# DAT_Replacement.net
KiCad netlist of a schematic drawn in EAGLE
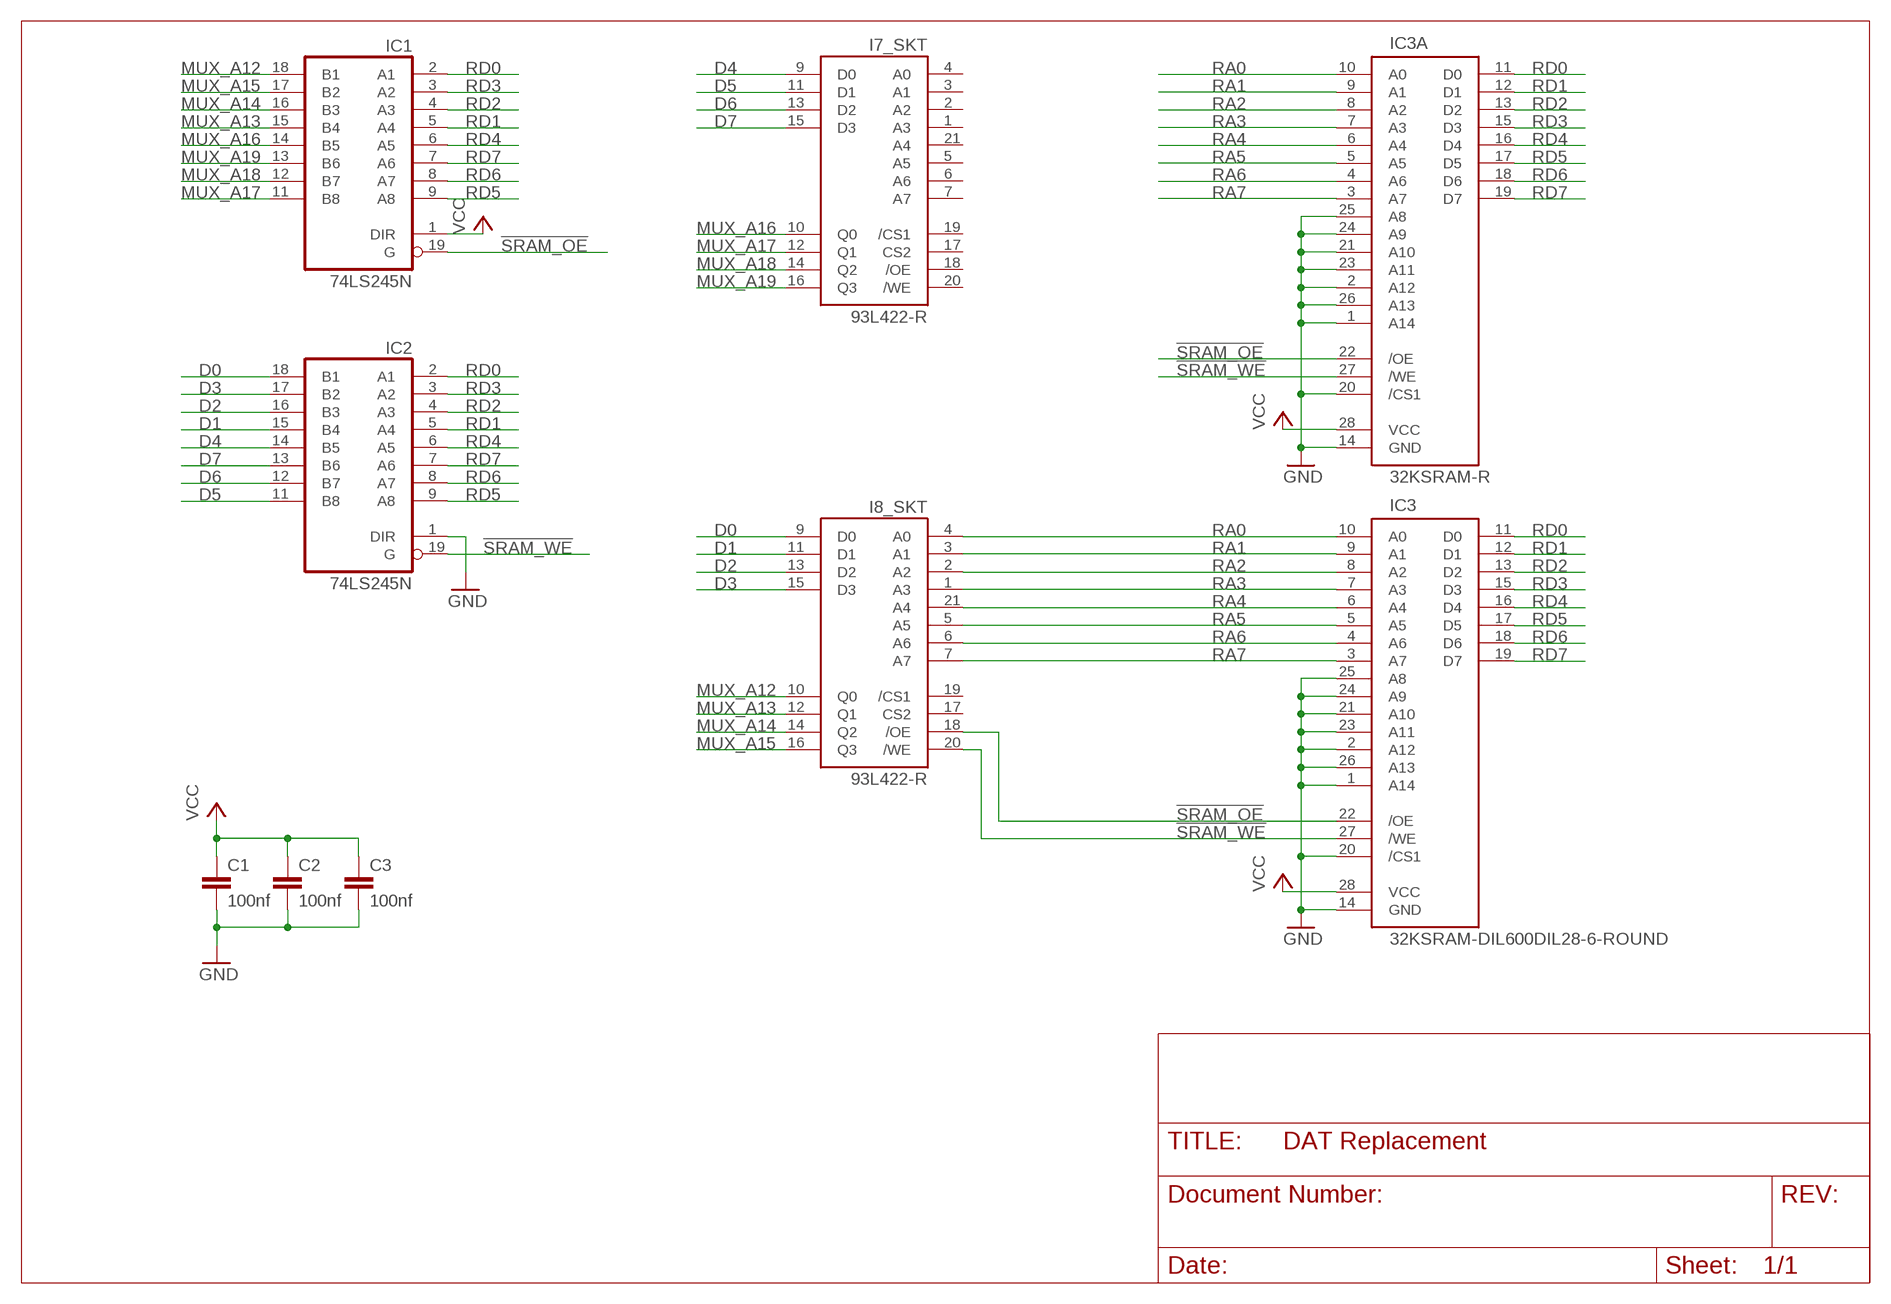
[diagram p0: schematic, sheet 1]

(export (version "E")
  (design (tool "Eeschema 10.0.6"))
  (components
    (comp (ref "C1")
      (value "100nf")
      (footprint "eagle-import:C025-025X050")
      (libsource (lib "eagle-import") (part "C-EU025-025X050"))
    )
    (comp (ref "C2")
      (value "100nf")
      (footprint "eagle-import:C025-025X050")
      (libsource (lib "eagle-import") (part "C-EU025-025X050"))
    )
    (comp (ref "C3")
      (value "100nf")
      (footprint "eagle-import:C025-025X050")
      (libsource (lib "eagle-import") (part "C-EU025-025X050"))
    )
    (comp (ref "I7_SKT")
      (value "93L422-R")
      (footprint "eagle-import:DIL-22-4-ROUND")
      (libsource (lib "eagle-import") (part "93L422-R"))
    )
    (comp (ref "I8_SKT")
      (value "93L422-R")
      (footprint "eagle-import:DIL-22-4-ROUND")
      (libsource (lib "eagle-import") (part "93L422-R"))
    )
    (comp (ref "IC1")
      (value "74LS245N")
      (footprint "eagle-import:DIL20")
      (libsource (lib "eagle-import") (part "74245NLS"))
    )
    (comp (ref "IC2")
      (value "74LS245N")
      (footprint "eagle-import:DIL20")
      (libsource (lib "eagle-import") (part "74245NLS"))
    )
    (comp (ref "IC3")
      (value "32KSRAM-DIL600DIL28-6-ROUND")
      (footprint "eagle-import:DIL28-6-ROUND")
      (libsource (lib "eagle-import") (part "32KSRAM-DIL600DIL28-6-ROUND"))
    )
    (comp (ref "IC3A")
      (value "32KSRAM-R")
      (footprint "eagle-import:DIL28-3-ROUND")
      (libsource (lib "eagle-import") (part "32KSRAM-R"))
    )
  )
  (nets
    (net (code "1") (name "/D0") (class "Default")
      (node (ref "I8_SKT") (pin "9") (pinfunction "D0_9") (pintype "input"))
      (node (ref "IC2") (pin "18") (pinfunction "B1_18") (pintype "bidirectional"))
    )
    (net (code "2") (name "/D1") (class "Default")
      (node (ref "I8_SKT") (pin "11") (pinfunction "D1_11") (pintype "input"))
      (node (ref "IC2") (pin "15") (pinfunction "B4_15") (pintype "bidirectional"))
    )
    (net (code "3") (name "/D2") (class "Default")
      (node (ref "I8_SKT") (pin "13") (pinfunction "D2_13") (pintype "input"))
      (node (ref "IC2") (pin "16") (pinfunction "B3_16") (pintype "bidirectional"))
    )
    (net (code "4") (name "/D3") (class "Default")
      (node (ref "I8_SKT") (pin "15") (pinfunction "D3_15") (pintype "input"))
      (node (ref "IC2") (pin "17") (pinfunction "B2_17") (pintype "bidirectional"))
    )
    (net (code "5") (name "/D4") (class "Default")
      (node (ref "I7_SKT") (pin "9") (pinfunction "D0_9") (pintype "input"))
      (node (ref "IC2") (pin "14") (pinfunction "B5_14") (pintype "bidirectional"))
    )
    (net (code "6") (name "/D5") (class "Default")
      (node (ref "I7_SKT") (pin "11") (pinfunction "D1_11") (pintype "input"))
      (node (ref "IC2") (pin "11") (pinfunction "B8_11") (pintype "bidirectional"))
    )
    (net (code "7") (name "/D6") (class "Default")
      (node (ref "I7_SKT") (pin "13") (pinfunction "D2_13") (pintype "input"))
      (node (ref "IC2") (pin "12") (pinfunction "B7_12") (pintype "bidirectional"))
    )
    (net (code "8") (name "/D7") (class "Default")
      (node (ref "I7_SKT") (pin "15") (pinfunction "D3_15") (pintype "input"))
      (node (ref "IC2") (pin "13") (pinfunction "B6_13") (pintype "bidirectional"))
    )
    (net (code "9") (name "/MUX_A12") (class "Default")
      (node (ref "I8_SKT") (pin "10") (pinfunction "Q0_10") (pintype "output"))
      (node (ref "IC1") (pin "18") (pinfunction "B1_18") (pintype "bidirectional"))
    )
    (net (code "10") (name "/MUX_A13") (class "Default")
      (node (ref "I8_SKT") (pin "12") (pinfunction "Q1_12") (pintype "output"))
      (node (ref "IC1") (pin "15") (pinfunction "B4_15") (pintype "bidirectional"))
    )
    (net (code "11") (name "/MUX_A14") (class "Default")
      (node (ref "I8_SKT") (pin "14") (pinfunction "Q2_14") (pintype "output"))
      (node (ref "IC1") (pin "16") (pinfunction "B3_16") (pintype "bidirectional"))
    )
    (net (code "12") (name "/MUX_A15") (class "Default")
      (node (ref "I8_SKT") (pin "16") (pinfunction "Q3_16") (pintype "output"))
      (node (ref "IC1") (pin "17") (pinfunction "B2_17") (pintype "bidirectional"))
    )
    (net (code "13") (name "/MUX_A16") (class "Default")
      (node (ref "I7_SKT") (pin "10") (pinfunction "Q0_10") (pintype "output"))
      (node (ref "IC1") (pin "14") (pinfunction "B5_14") (pintype "bidirectional"))
    )
    (net (code "14") (name "/MUX_A17") (class "Default")
      (node (ref "I7_SKT") (pin "12") (pinfunction "Q1_12") (pintype "output"))
      (node (ref "IC1") (pin "11") (pinfunction "B8_11") (pintype "bidirectional"))
    )
    (net (code "15") (name "/MUX_A18") (class "Default")
      (node (ref "I7_SKT") (pin "14") (pinfunction "Q2_14") (pintype "output"))
      (node (ref "IC1") (pin "12") (pinfunction "B7_12") (pintype "bidirectional"))
    )
    (net (code "16") (name "/MUX_A19") (class "Default")
      (node (ref "I7_SKT") (pin "16") (pinfunction "Q3_16") (pintype "output"))
      (node (ref "IC1") (pin "13") (pinfunction "B6_13") (pintype "bidirectional"))
    )
    (net (code "17") (name "/RA0") (class "Default")
      (node (ref "I8_SKT") (pin "4") (pinfunction "A0_4") (pintype "input"))
      (node (ref "IC3") (pin "10") (pinfunction "A0_10") (pintype "input"))
      (node (ref "IC3A") (pin "10") (pinfunction "A0_10") (pintype "input"))
    )
    (net (code "18") (name "/RA1") (class "Default")
      (node (ref "I8_SKT") (pin "3") (pinfunction "A1_3") (pintype "input"))
      (node (ref "IC3") (pin "9") (pinfunction "A1_9") (pintype "input"))
      (node (ref "IC3A") (pin "9") (pinfunction "A1_9") (pintype "input"))
    )
    (net (code "19") (name "/RA2") (class "Default")
      (node (ref "I8_SKT") (pin "2") (pinfunction "A2_2") (pintype "input"))
      (node (ref "IC3") (pin "8") (pinfunction "A2_8") (pintype "input"))
      (node (ref "IC3A") (pin "8") (pinfunction "A2_8") (pintype "input"))
    )
    (net (code "20") (name "/RA3") (class "Default")
      (node (ref "I8_SKT") (pin "1") (pinfunction "A3_1") (pintype "input"))
      (node (ref "IC3") (pin "7") (pinfunction "A3_7") (pintype "input"))
      (node (ref "IC3A") (pin "7") (pinfunction "A3_7") (pintype "input"))
    )
    (net (code "21") (name "/RA4") (class "Default")
      (node (ref "I8_SKT") (pin "21") (pinfunction "A4_21") (pintype "input"))
      (node (ref "IC3") (pin "6") (pinfunction "A4_6") (pintype "input"))
      (node (ref "IC3A") (pin "6") (pinfunction "A4_6") (pintype "input"))
    )
    (net (code "22") (name "/RA5") (class "Default")
      (node (ref "I8_SKT") (pin "5") (pinfunction "A5_5") (pintype "input"))
      (node (ref "IC3") (pin "5") (pinfunction "A5_5") (pintype "input"))
      (node (ref "IC3A") (pin "5") (pinfunction "A5_5") (pintype "input"))
    )
    (net (code "23") (name "/RA6") (class "Default")
      (node (ref "I8_SKT") (pin "6") (pinfunction "A6_6") (pintype "input"))
      (node (ref "IC3") (pin "4") (pinfunction "A6_4") (pintype "input"))
      (node (ref "IC3A") (pin "4") (pinfunction "A6_4") (pintype "input"))
    )
    (net (code "24") (name "/RA7") (class "Default")
      (node (ref "I8_SKT") (pin "7") (pinfunction "A7_7") (pintype "input"))
      (node (ref "IC3") (pin "3") (pinfunction "A7_3") (pintype "input"))
      (node (ref "IC3A") (pin "3") (pinfunction "A7_3") (pintype "input"))
    )
    (net (code "25") (name "/RD0") (class "Default")
      (node (ref "IC1") (pin "2") (pinfunction "A1_2") (pintype "bidirectional"))
      (node (ref "IC2") (pin "2") (pinfunction "A1_2") (pintype "bidirectional"))
      (node (ref "IC3") (pin "11") (pinfunction "D0_11") (pintype "bidirectional"))
      (node (ref "IC3A") (pin "11") (pinfunction "D0_11") (pintype "bidirectional"))
    )
    (net (code "26") (name "/RD1") (class "Default")
      (node (ref "IC1") (pin "5") (pinfunction "A4_5") (pintype "bidirectional"))
      (node (ref "IC2") (pin "5") (pinfunction "A4_5") (pintype "bidirectional"))
      (node (ref "IC3") (pin "12") (pinfunction "D1_12") (pintype "bidirectional"))
      (node (ref "IC3A") (pin "12") (pinfunction "D1_12") (pintype "bidirectional"))
    )
    (net (code "27") (name "/RD2") (class "Default")
      (node (ref "IC1") (pin "4") (pinfunction "A3_4") (pintype "bidirectional"))
      (node (ref "IC2") (pin "4") (pinfunction "A3_4") (pintype "bidirectional"))
      (node (ref "IC3") (pin "13") (pinfunction "D2_13") (pintype "bidirectional"))
      (node (ref "IC3A") (pin "13") (pinfunction "D2_13") (pintype "bidirectional"))
    )
    (net (code "28") (name "/RD3") (class "Default")
      (node (ref "IC1") (pin "3") (pinfunction "A2_3") (pintype "bidirectional"))
      (node (ref "IC2") (pin "3") (pinfunction "A2_3") (pintype "bidirectional"))
      (node (ref "IC3") (pin "15") (pinfunction "D3_15") (pintype "bidirectional"))
      (node (ref "IC3A") (pin "15") (pinfunction "D3_15") (pintype "bidirectional"))
    )
    (net (code "29") (name "/RD4") (class "Default")
      (node (ref "IC1") (pin "6") (pinfunction "A5_6") (pintype "bidirectional"))
      (node (ref "IC2") (pin "6") (pinfunction "A5_6") (pintype "bidirectional"))
      (node (ref "IC3") (pin "16") (pinfunction "D4_16") (pintype "bidirectional"))
      (node (ref "IC3A") (pin "16") (pinfunction "D4_16") (pintype "bidirectional"))
    )
    (net (code "30") (name "/RD5") (class "Default")
      (node (ref "IC1") (pin "9") (pinfunction "A8_9") (pintype "bidirectional"))
      (node (ref "IC2") (pin "9") (pinfunction "A8_9") (pintype "bidirectional"))
      (node (ref "IC3") (pin "17") (pinfunction "D5_17") (pintype "bidirectional"))
      (node (ref "IC3A") (pin "17") (pinfunction "D5_17") (pintype "bidirectional"))
    )
    (net (code "31") (name "/RD6") (class "Default")
      (node (ref "IC1") (pin "8") (pinfunction "A7_8") (pintype "bidirectional"))
      (node (ref "IC2") (pin "8") (pinfunction "A7_8") (pintype "bidirectional"))
      (node (ref "IC3") (pin "18") (pinfunction "D6_18") (pintype "bidirectional"))
      (node (ref "IC3A") (pin "18") (pinfunction "D6_18") (pintype "bidirectional"))
    )
    (net (code "32") (name "/RD7") (class "Default")
      (node (ref "IC1") (pin "7") (pinfunction "A6_7") (pintype "bidirectional"))
      (node (ref "IC2") (pin "7") (pinfunction "A6_7") (pintype "bidirectional"))
      (node (ref "IC3") (pin "19") (pinfunction "D7_19") (pintype "bidirectional"))
      (node (ref "IC3A") (pin "19") (pinfunction "D7_19") (pintype "bidirectional"))
    )
    (net (code "33") (name "/~{SRAM_OE}") (class "Default")
      (node (ref "I8_SKT") (pin "18") (pinfunction "/OE_18") (pintype "input"))
      (node (ref "IC1") (pin "19") (pinfunction "G_19") (pintype "input"))
      (node (ref "IC3") (pin "22") (pinfunction "/OE_22") (pintype "input"))
      (node (ref "IC3A") (pin "22") (pinfunction "/OE_22") (pintype "input"))
    )
    (net (code "34") (name "/~{SRAM_WE}") (class "Default")
      (node (ref "I8_SKT") (pin "20") (pinfunction "/WE_20") (pintype "input"))
      (node (ref "IC2") (pin "19") (pinfunction "G_19") (pintype "input"))
      (node (ref "IC3") (pin "27") (pinfunction "/WE_27") (pintype "input"))
      (node (ref "IC3A") (pin "27") (pinfunction "/WE_27") (pintype "input"))
    )
    (net (code "35") (name "GND") (class "Default")
      (node (ref "C1") (pin "2") (pinfunction "2_2") (pintype "passive"))
      (node (ref "C2") (pin "2") (pinfunction "2_2") (pintype "passive"))
      (node (ref "C3") (pin "2") (pinfunction "2_2") (pintype "passive"))
      (node (ref "IC2") (pin "1") (pinfunction "DIR_1") (pintype "input"))
      (node (ref "IC3") (pin "1") (pinfunction "A14_1") (pintype "input"))
      (node (ref "IC3") (pin "14") (pinfunction "GND_14") (pintype "power_in"))
      (node (ref "IC3") (pin "2") (pinfunction "A12_2") (pintype "input"))
      (node (ref "IC3") (pin "20") (pinfunction "/CS1_20") (pintype "input"))
      (node (ref "IC3") (pin "21") (pinfunction "A10_21") (pintype "input"))
      (node (ref "IC3") (pin "23") (pinfunction "A11_23") (pintype "input"))
      (node (ref "IC3") (pin "24") (pinfunction "A9_24") (pintype "input"))
      (node (ref "IC3") (pin "25") (pinfunction "A8_25") (pintype "input"))
      (node (ref "IC3") (pin "26") (pinfunction "A13_26") (pintype "input"))
      (node (ref "IC3A") (pin "1") (pinfunction "A14_1") (pintype "input"))
      (node (ref "IC3A") (pin "14") (pinfunction "GND_14") (pintype "power_in"))
      (node (ref "IC3A") (pin "2") (pinfunction "A12_2") (pintype "input"))
      (node (ref "IC3A") (pin "20") (pinfunction "/CS1_20") (pintype "input"))
      (node (ref "IC3A") (pin "21") (pinfunction "A10_21") (pintype "input"))
      (node (ref "IC3A") (pin "23") (pinfunction "A11_23") (pintype "input"))
      (node (ref "IC3A") (pin "24") (pinfunction "A9_24") (pintype "input"))
      (node (ref "IC3A") (pin "25") (pinfunction "A8_25") (pintype "input"))
      (node (ref "IC3A") (pin "26") (pinfunction "A13_26") (pintype "input"))
    )
    (net (code "36") (name "VCC") (class "Default")
      (node (ref "C1") (pin "1") (pinfunction "1_1") (pintype "passive"))
      (node (ref "C2") (pin "1") (pinfunction "1_1") (pintype "passive"))
      (node (ref "C3") (pin "1") (pinfunction "1_1") (pintype "passive"))
      (node (ref "IC1") (pin "1") (pinfunction "DIR_1") (pintype "input"))
      (node (ref "IC3") (pin "28") (pinfunction "VCC_28") (pintype "power_in"))
      (node (ref "IC3A") (pin "28") (pinfunction "VCC_28") (pintype "power_in"))
    )
    (net (code "37") (name "unconnected-(I7_SKTA-A0-Pad4)") (class "Default")
      (node (ref "I7_SKT") (pin "4") (pinfunction "A0_4") (pintype "input"))
    )
    (net (code "38") (name "unconnected-(I7_SKTA-A1-Pad3)") (class "Default")
      (node (ref "I7_SKT") (pin "3") (pinfunction "A1_3") (pintype "input"))
    )
    (net (code "39") (name "unconnected-(I7_SKTA-A2-Pad2)") (class "Default")
      (node (ref "I7_SKT") (pin "2") (pinfunction "A2_2") (pintype "input"))
    )
    (net (code "40") (name "unconnected-(I7_SKTA-A3-Pad1)") (class "Default")
      (node (ref "I7_SKT") (pin "1") (pinfunction "A3_1") (pintype "input"))
    )
    (net (code "41") (name "unconnected-(I7_SKTA-A4-Pad21)") (class "Default")
      (node (ref "I7_SKT") (pin "21") (pinfunction "A4_21") (pintype "input"))
    )
    (net (code "42") (name "unconnected-(I7_SKTA-A5-Pad5)") (class "Default")
      (node (ref "I7_SKT") (pin "5") (pinfunction "A5_5") (pintype "input"))
    )
    (net (code "43") (name "unconnected-(I7_SKTA-A6-Pad6)") (class "Default")
      (node (ref "I7_SKT") (pin "6") (pinfunction "A6_6") (pintype "input"))
    )
    (net (code "44") (name "unconnected-(I7_SKTA-A7-Pad7)") (class "Default")
      (node (ref "I7_SKT") (pin "7") (pinfunction "A7_7") (pintype "input"))
    )
    (net (code "45") (name "unconnected-(I7_SKTA-CS2-Pad17)") (class "Default")
      (node (ref "I7_SKT") (pin "17") (pinfunction "CS2_17") (pintype "input"))
    )
    (net (code "46") (name "unconnected-(I7_SKTA-{slash}CS1-Pad19)") (class "Default")
      (node (ref "I7_SKT") (pin "19") (pinfunction "/CS1_19") (pintype "input"))
    )
    (net (code "47") (name "unconnected-(I7_SKTA-{slash}OE-Pad18)") (class "Default")
      (node (ref "I7_SKT") (pin "18") (pinfunction "/OE_18") (pintype "input"))
    )
    (net (code "48") (name "unconnected-(I7_SKTA-{slash}WE-Pad20)") (class "Default")
      (node (ref "I7_SKT") (pin "20") (pinfunction "/WE_20") (pintype "input"))
    )
    (net (code "49") (name "unconnected-(I8_SKTA-CS2-Pad17)") (class "Default")
      (node (ref "I8_SKT") (pin "17") (pinfunction "CS2_17") (pintype "input"))
    )
    (net (code "50") (name "unconnected-(I8_SKTA-{slash}CS1-Pad19)") (class "Default")
      (node (ref "I8_SKT") (pin "19") (pinfunction "/CS1_19") (pintype "input"))
    )
  )
)
